# hello_marco.net
KiCad netlist of a schematic drawn in EAGLE
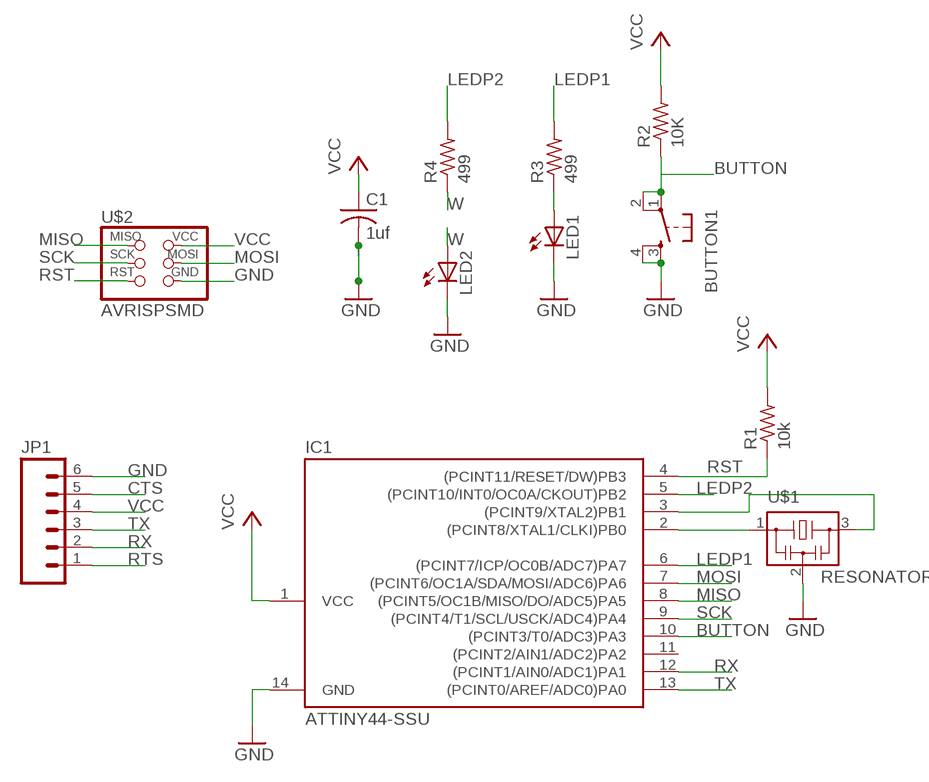
[diagram p0: schematic, sheet 1]

(export (version "E")
  (design (tool "Eeschema 10.0.6"))
  (components
    (comp (ref "BUTTON1")
      (value "6MM_SWITCH6MM_SWITCH")
      (footprint "eagle-import:6MM_SWITCH")
      (libsource (lib "eagle-import") (part "6MM_SWITCH6MM_SWITCH"))
    )
    (comp (ref "C1")
      (value "1uf")
      (footprint "eagle-import:C1206")
      (libsource (lib "eagle-import") (part "C-USC1206"))
    )
    (comp (ref "IC1")
      (value "ATTINY44-SSU")
      (footprint "eagle-import:SOIC14")
      (libsource (lib "eagle-import") (part "ATTINY44-SSU"))
    )
    (comp (ref "JP1")
      (value "M06SMD")
      (footprint "eagle-import:1X06-SMD")
      (libsource (lib "eagle-import") (part "M06SMD"))
    )
    (comp (ref "LED1")
      (value "LED1206")
      (footprint "eagle-import:1206")
      (libsource (lib "eagle-import") (part "LED1206"))
    )
    (comp (ref "LED2")
      (value "LED1206")
      (footprint "eagle-import:1206")
      (libsource (lib "eagle-import") (part "LED1206"))
    )
    (comp (ref "R1")
      (value "10k")
      (footprint "eagle-import:R1206")
      (libsource (lib "eagle-import") (part "R-US_R1206"))
    )
    (comp (ref "R2")
      (value "10K")
      (footprint "eagle-import:1206")
      (libsource (lib "eagle-import") (part "RESISTOR1206"))
    )
    (comp (ref "R3")
      (value "499")
      (footprint "eagle-import:1206")
      (libsource (lib "eagle-import") (part "RESISTOR1206"))
    )
    (comp (ref "R4")
      (value "499")
      (footprint "eagle-import:1206")
      (libsource (lib "eagle-import") (part "RESISTOR1206"))
    )
    (comp (ref "U$1")
      (value "RESONATOR")
      (footprint "eagle-import:EFOBM")
      (libsource (lib "eagle-import") (part "RESONATOR"))
    )
    (comp (ref "U$2")
      (value "AVRISPSMD")
      (footprint "eagle-import:2X03SMD")
      (libsource (lib "eagle-import") (part "AVRISPSMD"))
    )
  )
  (nets
    (net (code "1") (name "/BUTTON") (class "Default")
      (node (ref "IC1") (pin "10") (pinfunction "(PCINT3/T0/ADC3)PA3_10") (pintype "bidirectional"))
    )
    (net (code "2") (name "/CTS") (class "Default")
      (node (ref "JP1") (pin "5") (pinfunction "5_5") (pintype "passive"))
    )
    (net (code "3") (name "/LEDP1") (class "Default")
      (node (ref "IC1") (pin "6") (pinfunction "(PCINT7/ICP/OC0B/ADC7)PA7_6") (pintype "bidirectional"))
      (node (ref "R3") (pin "2") (pinfunction "2_2") (pintype "passive"))
    )
    (net (code "4") (name "/LEDP2") (class "Default")
      (node (ref "IC1") (pin "5") (pinfunction "(PCINT10/INT0/OC0A/CKOUT)PB2_5") (pintype "bidirectional"))
      (node (ref "R4") (pin "2") (pinfunction "2_2") (pintype "passive"))
    )
    (net (code "5") (name "/MISO") (class "Default")
      (node (ref "IC1") (pin "8") (pinfunction "(PCINT5/OC1B/MISO/DO/ADC5)PA5_8") (pintype "bidirectional"))
      (node (ref "U$2") (pin "1") (pinfunction "MISO_1") (pintype "passive"))
    )
    (net (code "6") (name "/MOSI") (class "Default")
      (node (ref "IC1") (pin "7") (pinfunction "(PCINT6/OC1A/SDA/MOSI/ADC6)PA6_7") (pintype "bidirectional"))
      (node (ref "U$2") (pin "4") (pinfunction "MOSI_4") (pintype "passive"))
    )
    (net (code "7") (name "/RST") (class "Default")
      (node (ref "IC1") (pin "4") (pinfunction "(PCINT11/RESET/DW)PB3_4") (pintype "bidirectional"))
      (node (ref "R1") (pin "1") (pinfunction "1_1") (pintype "passive"))
      (node (ref "U$2") (pin "5") (pinfunction "RST_5") (pintype "passive"))
    )
    (net (code "8") (name "/RTS") (class "Default")
      (node (ref "JP1") (pin "1") (pinfunction "1_1") (pintype "passive"))
    )
    (net (code "9") (name "/RX") (class "Default")
      (node (ref "IC1") (pin "12") (pinfunction "(PCINT1/AIN0/ADC1)PA1_12") (pintype "bidirectional"))
      (node (ref "JP1") (pin "2") (pinfunction "2_2") (pintype "passive"))
    )
    (net (code "10") (name "/SCK") (class "Default")
      (node (ref "IC1") (pin "9") (pinfunction "(PCINT4/T1/SCL/USCK/ADC4)PA4_9") (pintype "bidirectional"))
      (node (ref "U$2") (pin "3") (pinfunction "SCK_3") (pintype "passive"))
    )
    (net (code "11") (name "/TX") (class "Default")
      (node (ref "IC1") (pin "13") (pinfunction "(PCINT0/AREF/ADC0)PA0_13") (pintype "bidirectional"))
      (node (ref "JP1") (pin "3") (pinfunction "3_3") (pintype "passive"))
    )
    (net (code "12") (name "/W") (class "Default")
      (node (ref "LED2") (pin "1") (pinfunction "A_1") (pintype "passive"))
      (node (ref "R4") (pin "1") (pinfunction "1_1") (pintype "passive"))
    )
    (net (code "13") (name "GND") (class "Default")
      (node (ref "BUTTON1") (pin "3") (pinfunction "S_3") (pintype "passive"))
      (node (ref "BUTTON1") (pin "4") (pinfunction "S1_4") (pintype "passive"))
      (node (ref "C1") (pin "2") (pinfunction "2_2") (pintype "passive"))
      (node (ref "IC1") (pin "14") (pinfunction "GND_14") (pintype "power_in"))
      (node (ref "JP1") (pin "6") (pinfunction "6_6") (pintype "passive"))
      (node (ref "LED1") (pin "2") (pinfunction "C_2") (pintype "passive"))
      (node (ref "LED2") (pin "2") (pinfunction "C_2") (pintype "passive"))
      (node (ref "U$1") (pin "2") (pinfunction "2_2") (pintype "passive"))
      (node (ref "U$2") (pin "6") (pinfunction "GND_6") (pintype "passive"))
    )
    (net (code "14") (name "Net-(BUTTON1-P)") (class "Default")
      (node (ref "BUTTON1") (pin "1") (pinfunction "P_1") (pintype "passive"))
      (node (ref "BUTTON1") (pin "2") (pinfunction "P1_2") (pintype "passive"))
      (node (ref "R2") (pin "1") (pinfunction "1_1") (pintype "passive"))
    )
    (net (code "15") (name "Net-(IC1-(PCINT8{slash}XTAL1{slash}CLKI)PB0)") (class "Default")
      (node (ref "IC1") (pin "2") (pinfunction "(PCINT8/XTAL1/CLKI)PB0_2") (pintype "bidirectional"))
      (node (ref "U$1") (pin "1") (pinfunction "1_1") (pintype "passive"))
    )
    (net (code "16") (name "Net-(IC1-(PCINT9{slash}XTAL2)PB1)") (class "Default")
      (node (ref "IC1") (pin "3") (pinfunction "(PCINT9/XTAL2)PB1_3") (pintype "bidirectional"))
      (node (ref "U$1") (pin "3") (pinfunction "3_3") (pintype "passive"))
    )
    (net (code "17") (name "Net-(LED1-A)") (class "Default")
      (node (ref "LED1") (pin "1") (pinfunction "A_1") (pintype "passive"))
      (node (ref "R3") (pin "1") (pinfunction "1_1") (pintype "passive"))
    )
    (net (code "18") (name "VCC") (class "Default")
      (node (ref "C1") (pin "1") (pinfunction "1_1") (pintype "passive"))
      (node (ref "IC1") (pin "1") (pinfunction "VCC_1") (pintype "power_in"))
      (node (ref "JP1") (pin "4") (pinfunction "4_4") (pintype "passive"))
      (node (ref "R1") (pin "2") (pinfunction "2_2") (pintype "passive"))
      (node (ref "R2") (pin "2") (pinfunction "2_2") (pintype "passive"))
      (node (ref "U$2") (pin "2") (pinfunction "VCC_2") (pintype "passive"))
    )
    (net (code "19") (name "unconnected-(IC1-(PCINT2{slash}AIN1{slash}ADC2)PA2-Pad11)") (class "Default")
      (node (ref "IC1") (pin "11") (pinfunction "(PCINT2/AIN1/ADC2)PA2_11") (pintype "bidirectional"))
    )
  )
)
